# Top.net
KiCad netlist of a schematic drawn in Altium Designer
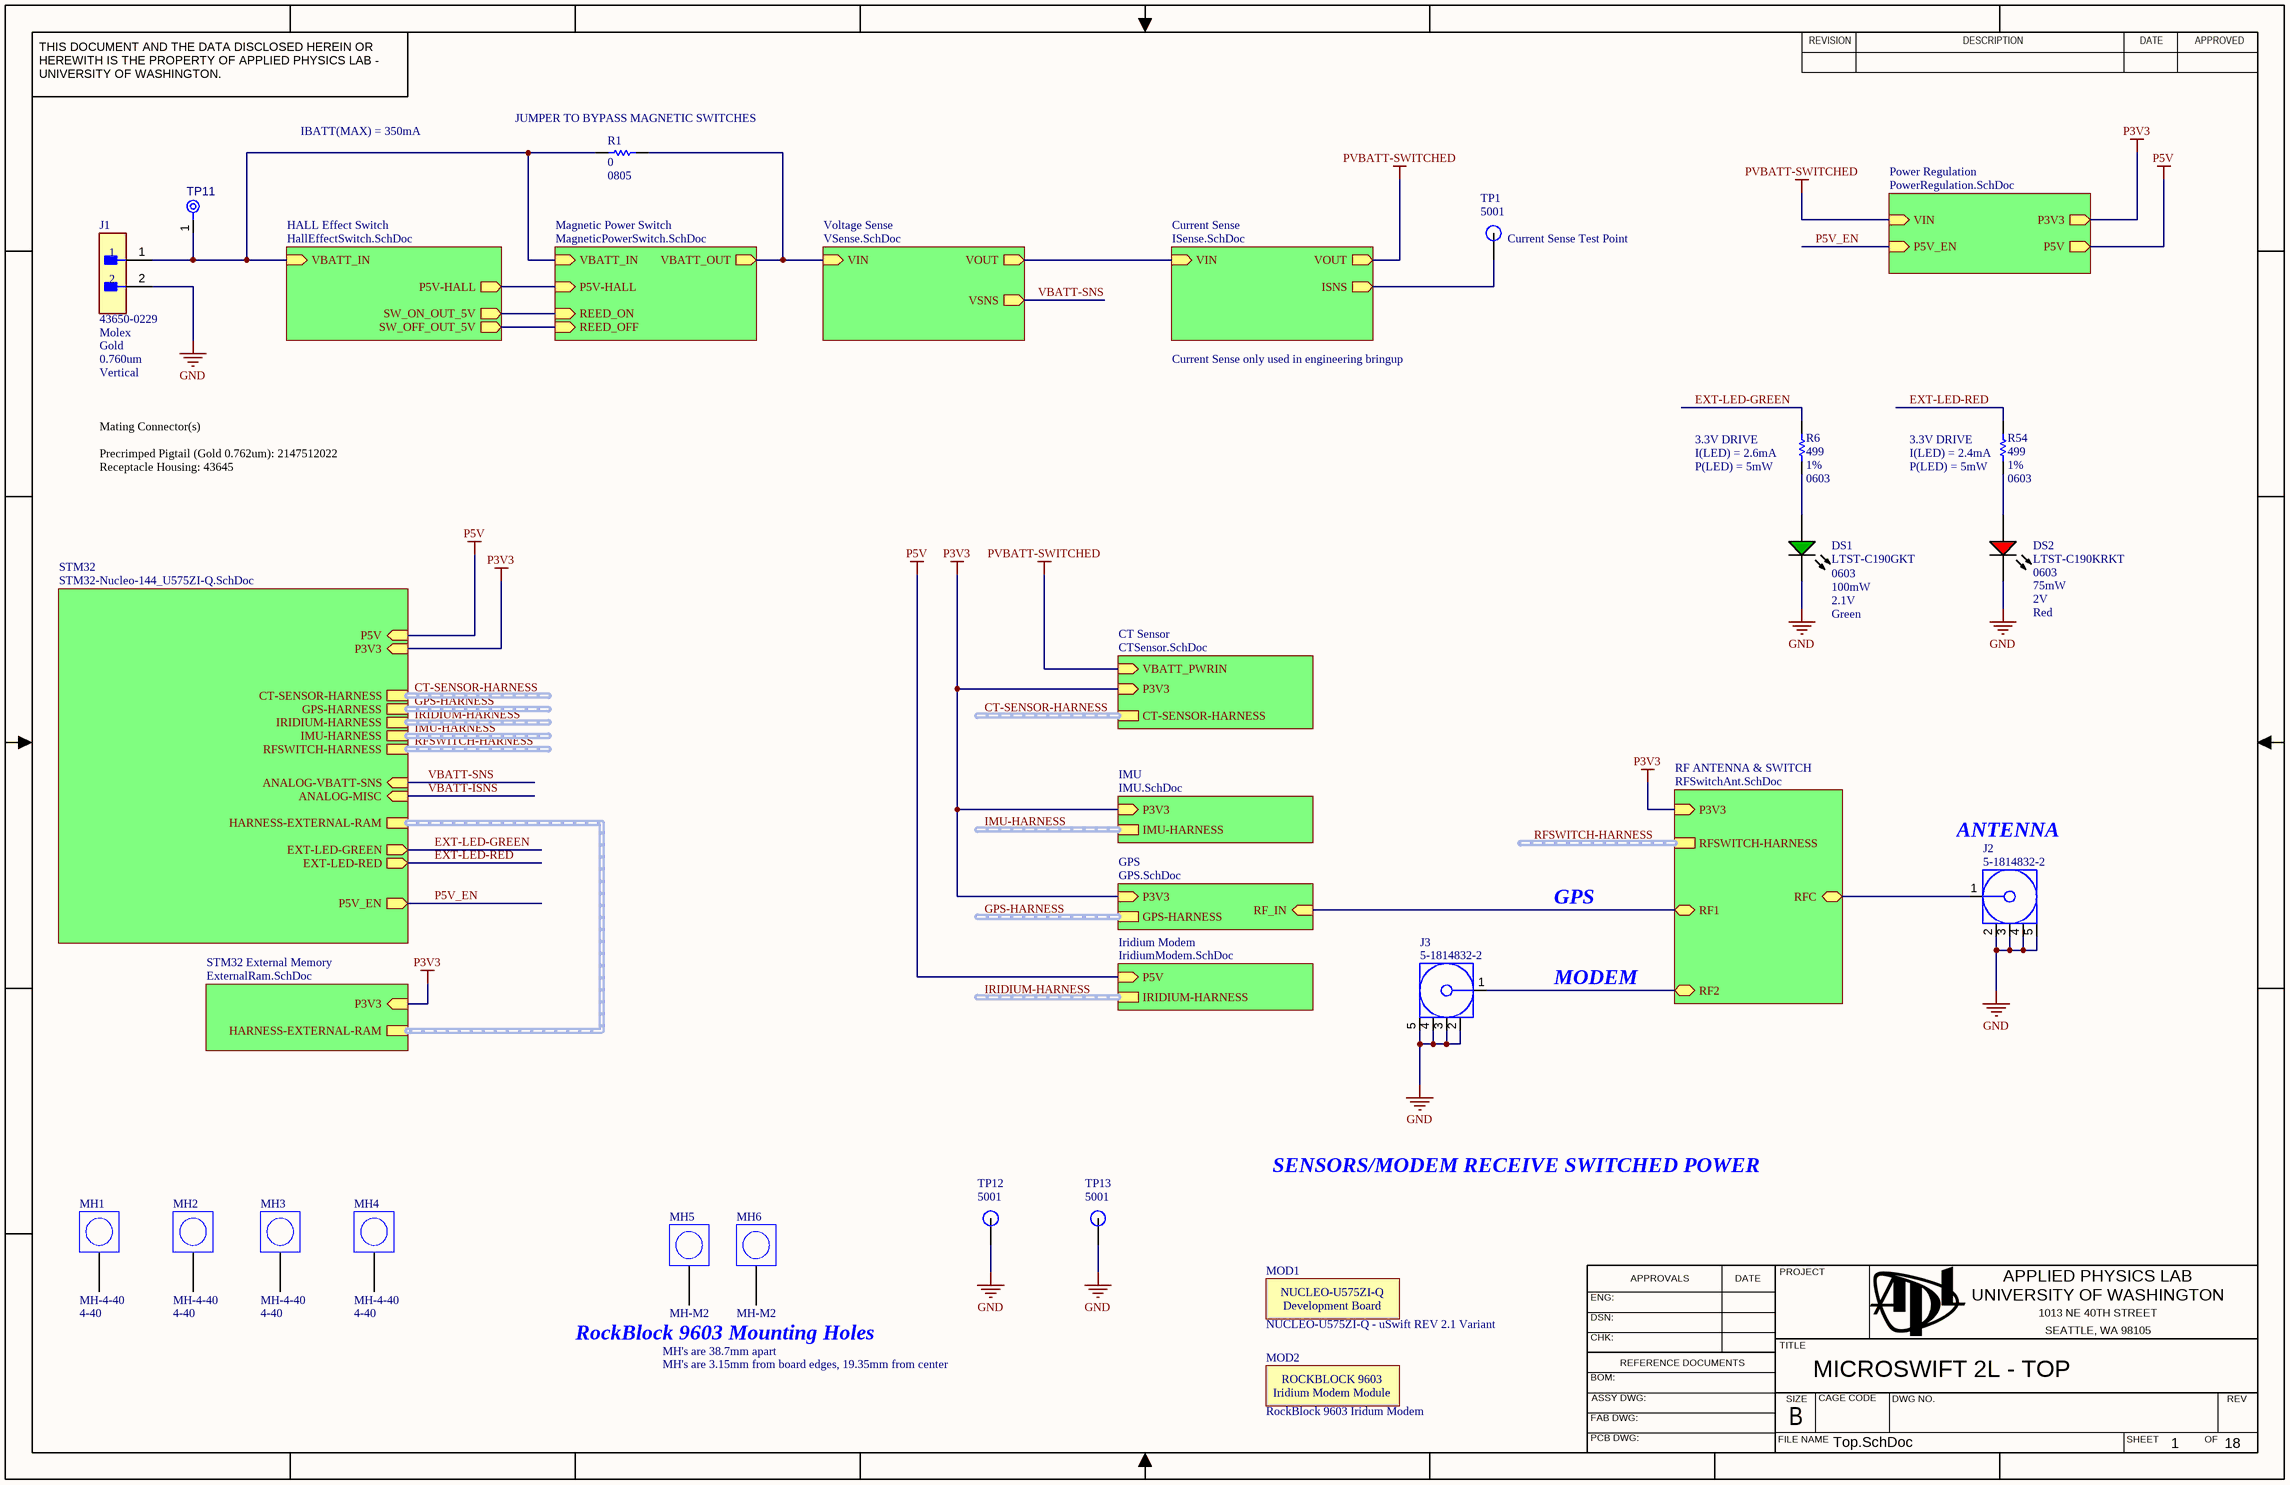
[diagram p0: Top.SchDoc]

(export (version "E")
  (design (tool "Eeschema 10.0.6"))
  (components
    (comp (ref "DS1")
      (value "LTST-C190GKT")
      (footprint "LTST-C190GKT_V")
      (description "LED Uni-Color Green, 100 mW, 30 mA, -55 to 85 degC, 2-Pin SMD, RoHS, Tape and Reel")
      (fields
        (field (name "POWER") "100mW")
        (field (name "COLOUR") "Green")
        (field (name "FORWARD VOLTAGE") "2.1V")
        (field (name "CASE/PACKAGE") "0603")
        (field (name "MANUFACTURER") "Lite-On")
      )
      (libsource (lib "Applied Physics Lab") (part "LED-GREEN-AK-2"))
    )
    (comp (ref "DS2")
      (value "LTST-C190KRKT")
      (footprint "LTST-C191KRKT_V")
      (description "LED Uni-Color Red, 62.5 mW, 25 mA, -30 to 85 degC, 2-Pin SMD, RoHS, Tape and Reel")
      (fields
        (field (name "CASE/PACKAGE") "0603")
        (field (name "POWER") "75mW")
        (field (name "MANUFACTURER") "Lite-On")
        (field (name "FORWARD VOLTAGE") "2V")
        (field (name "ILLUMINATION COLOUR") "Red")
      )
      (libsource (lib "Applied Physics Lab") (part "LED-RED-AK-2"))
    )
    (comp (ref "J1")
      (value "43650-0229")
      (footprint "FP-43650-0229-MFG")
      (description "Conn Wire to Board HDR 2 POS 3mm Solder ST Top Entry Thru-Hole Micro-Fit 3.0 Tray")
      (fields
        (field (name "MANUFACTURER") "Molex")
        (field (name "CONTACT PLATING") "Gold")
        (field (name "PLATING THICKNESS") "0.760um")
        (field (name "ORIENTATION") "Vertical")
      )
      (libsource (lib "Applied Physics Lab") (part "3bc925449376181038e59eaffc5286c"))
    )
    (comp (ref "J2")
      (value "5-1814832-2")
      (footprint "FP-5-1814832-2-MFG")
      (description "SMA Connector Jack, Female Socket 50Ohm Through Hole Solder")
      (fields (field (name "MANUFACTURER") "TE Connectivity"))
      (libsource (lib "Applied Physics Lab") (part "CN-S-4F-RF5"))
    )
    (comp (ref "J3")
      (value "5-1814832-2")
      (footprint "FP-5-1814832-2-MFG")
      (description "SMA Connector Jack, Female Socket 50Ohm Through Hole Solder")
      (fields (field (name "MANUFACTURER") "TE Connectivity"))
      (libsource (lib "Applied Physics Lab") (part "CN-S-4F-RF5"))
    )
    (comp (ref "MH1")
      (value "MH-4-40")
      (footprint "MH-4-40-Footprint")
      (description "4-40 plated mounting hole with button head pad.")
      (fields (field (name "FASTENER SIZE") "4-40"))
      (libsource (lib "Applied Physics Lab") (part "MH-Symbol-1"))
    )
    (comp (ref "MH2")
      (value "MH-4-40")
      (footprint "MH-4-40-Footprint")
      (description "4-40 plated mounting hole with button head pad.")
      (fields (field (name "FASTENER SIZE") "4-40"))
      (libsource (lib "Applied Physics Lab") (part "MH-Symbol-1"))
    )
    (comp (ref "MH3")
      (value "MH-4-40")
      (footprint "MH-4-40-Footprint")
      (description "4-40 plated mounting hole with button head pad.")
      (fields (field (name "FASTENER SIZE") "4-40"))
      (libsource (lib "Applied Physics Lab") (part "MH-Symbol-1"))
    )
    (comp (ref "MH4")
      (value "MH-4-40")
      (footprint "MH-4-40-Footprint")
      (description "4-40 plated mounting hole with button head pad.")
      (fields (field (name "FASTENER SIZE") "4-40"))
      (libsource (lib "Applied Physics Lab") (part "MH-Symbol-1"))
    )
    (comp (ref "MH5")
      (value "MH-M2")
      (footprint "MH-M2-Footprint")
      (description "M2 plated mounting hole.")
      (libsource (lib "Applied Physics Lab") (part "MH-Symbol-1"))
    )
    (comp (ref "MH6")
      (value "MH-M2")
      (footprint "MH-M2-Footprint")
      (description "M2 plated mounting hole.")
      (libsource (lib "Applied Physics Lab") (part "MH-Symbol-1"))
    )
    (comp (ref "MOD1")
      (value "NUCLEO-U575ZI-Q - uSwift REV 2.1 Variant")
      (footprint "NUCLEO-U575ZI-Q - uSwift REV 2.1 Variant")
      (libsource (lib "Applied Physics Lab") (part "STM32 NUCLEO-U575ZI-Q uSwift Variant"))
    )
    (comp (ref "MOD2")
      (value "RockBlock 9603 Iridum Modem")
      (footprint "RockBlock 9603")
      (description "RockBlock 9603 Iridium Modem")
      (libsource (lib "Applied Physics Lab") (part "RockBlock 9603"))
    )
    (comp (ref "R1")
      (value "0")
      (footprint "RESC2013X60X35ML10T20")
      (description "Chip Resistor, 0 Ohm, 0.125 W, -55 to 155 degC, 0805 (2012 Metric)")
      (fields
        (field (name "POWER") "125mW")
        (field (name "CASE/PACKAGE") "0805")
        (field (name "TOLERANCE") "5%")
      )
      (libsource (lib "Applied Physics Lab") (part "RES-2"))
    )
    (comp (ref "R6")
      (value "499")
      (footprint "RESC1609X50X30ML08T20")
      (description "Chip Resistor, 499 Ohm, +/- 1%, 0.1 W, -55 to 155 degC, 0603 (1608 Metric)")
      (fields
        (field (name "POWER") "100mW")
        (field (name "TOLERANCE") "1%")
        (field (name "CASE/PACKAGE") "0603")
        (field (name "Comment") "Resistor 499R +/-1% 0603 100 mW")
      )
      (libsource (lib "Applied Physics Lab") (part "RES-2"))
    )
    (comp (ref "R54")
      (value "499")
      (footprint "RESC1609X50X30ML08T20")
      (description "Chip Resistor, 499 Ohm, +/- 1%, 0.1 W, -55 to 155 degC, 0603 (1608 Metric)")
      (fields
        (field (name "POWER") "100mW")
        (field (name "TOLERANCE") "1%")
        (field (name "CASE/PACKAGE") "0603")
        (field (name "Comment") "Resistor 499R +/-1% 0603 100 mW")
      )
      (libsource (lib "Applied Physics Lab") (part "RES-2"))
    )
    (comp (ref "TP1")
      (value "5001")
      (footprint "FP-5001-MFG")
      (description "TEST POINT PC MINI .040D BLACK")
      (libsource (lib "Applied Physics Lab") (part "TestPoint-5005-Symbol-1"))
    )
    (comp (ref "TP11")
      (value "TPAD6R-CIRCLED")
      (footprint "TP06R - Circled")
      (description "0.6mm round with a silkscreen circle.")
      (libsource (lib "Applied Physics Lab") (part "CMP-001-0001-4"))
    )
    (comp (ref "TP12")
      (value "5001")
      (footprint "FP-5001-MFG")
      (description "TEST POINT PC MINI .040D BLACK")
      (libsource (lib "Applied Physics Lab") (part "TestPoint-5005-Symbol-1"))
    )
    (comp (ref "TP13")
      (value "5001")
      (footprint "FP-5001-MFG")
      (description "TEST POINT PC MINI .040D BLACK")
      (libsource (lib "Applied Physics Lab") (part "TestPoint-5005-Symbol-1"))
    )
  )
  (nets
    (net (code "6") (name "/EXT-LED-GREEN") (class "Default")
      (node (ref "R6") (pin "1") (pinfunction "1_1") (pintype "passive"))
    )
    (net (code "7") (name "/EXT-LED-RED") (class "Default")
      (node (ref "R54") (pin "1") (pinfunction "1_1") (pintype "passive"))
    )
    (net (code "9") (name "/ISNS") (class "Default")
      (node (ref "TP1") (pin "1") (pinfunction "1_1") (pintype "passive"))
    )
    (net (code "13") (name "/RF2") (class "Default")
      (node (ref "J3") (pin "1") (pinfunction "1_1") (pintype "passive"))
    )
    (net (code "14") (name "/RFC") (class "Default")
      (node (ref "J2") (pin "1") (pinfunction "1_1") (pintype "passive"))
    )
    (net (code "19") (name "/VBATT_IN") (class "Default")
      (node (ref "J1") (pin "1") (pinfunction "1_1") (pintype "passive"))
      (node (ref "R1") (pin "1") (pinfunction "1_1") (pintype "passive"))
      (node (ref "TP11") (pin "1") (pinfunction "TP_1") (pintype "passive"))
    )
    (net (code "20") (name "/VBATT_OUT") (class "Default")
      (node (ref "R1") (pin "2") (pinfunction "2_2") (pintype "passive"))
    )
    (net (code "27") (name "GND") (class "Default")
      (node (ref "DS1") (pin "2") (pinfunction "K_2") (pintype "passive"))
      (node (ref "DS2") (pin "2") (pinfunction "K_2") (pintype "passive"))
      (node (ref "J1") (pin "2") (pinfunction "2_2") (pintype "passive"))
      (node (ref "J2") (pin "2") (pinfunction "2_2") (pintype "passive"))
      (node (ref "J2") (pin "3") (pinfunction "3_3") (pintype "passive"))
      (node (ref "J2") (pin "4") (pinfunction "4_4") (pintype "passive"))
      (node (ref "J2") (pin "5") (pinfunction "5_5") (pintype "passive"))
      (node (ref "J3") (pin "2") (pinfunction "2_2") (pintype "passive"))
      (node (ref "J3") (pin "3") (pinfunction "3_3") (pintype "passive"))
      (node (ref "J3") (pin "4") (pinfunction "4_4") (pintype "passive"))
      (node (ref "J3") (pin "5") (pinfunction "5_5") (pintype "passive"))
      (node (ref "TP12") (pin "1") (pinfunction "1_1") (pintype "passive"))
      (node (ref "TP13") (pin "1") (pinfunction "1_1") (pintype "passive"))
    )
    (net (code "28") (name "Net-(DS1-A)") (class "Default")
      (node (ref "DS1") (pin "1") (pinfunction "A_1") (pintype "passive"))
      (node (ref "R6") (pin "2") (pinfunction "2_2") (pintype "passive"))
    )
    (net (code "29") (name "Net-(DS2-A)") (class "Default")
      (node (ref "DS2") (pin "1") (pinfunction "A_1") (pintype "passive"))
      (node (ref "R54") (pin "2") (pinfunction "2_2") (pintype "passive"))
    )
    (net (code "33") (name "unconnected-(MH1-Pad1)") (class "Default")
      (node (ref "MH1") (pin "1") (pinfunction "1_1") (pintype "passive"))
    )
    (net (code "34") (name "unconnected-(MH2-Pad1)") (class "Default")
      (node (ref "MH2") (pin "1") (pinfunction "1_1") (pintype "passive"))
    )
    (net (code "35") (name "unconnected-(MH3-Pad1)") (class "Default")
      (node (ref "MH3") (pin "1") (pinfunction "1_1") (pintype "passive"))
    )
    (net (code "36") (name "unconnected-(MH4-Pad1)") (class "Default")
      (node (ref "MH4") (pin "1") (pinfunction "1_1") (pintype "passive"))
    )
    (net (code "37") (name "unconnected-(MH5-Pad1)") (class "Default")
      (node (ref "MH5") (pin "1") (pinfunction "1_1") (pintype "passive"))
    )
    (net (code "38") (name "unconnected-(MH6-Pad1)") (class "Default")
      (node (ref "MH6") (pin "1") (pinfunction "1_1") (pintype "passive"))
    )
  )
)
